# hdreader.net
KiCad netlist of a schematic drawn in EAGLE
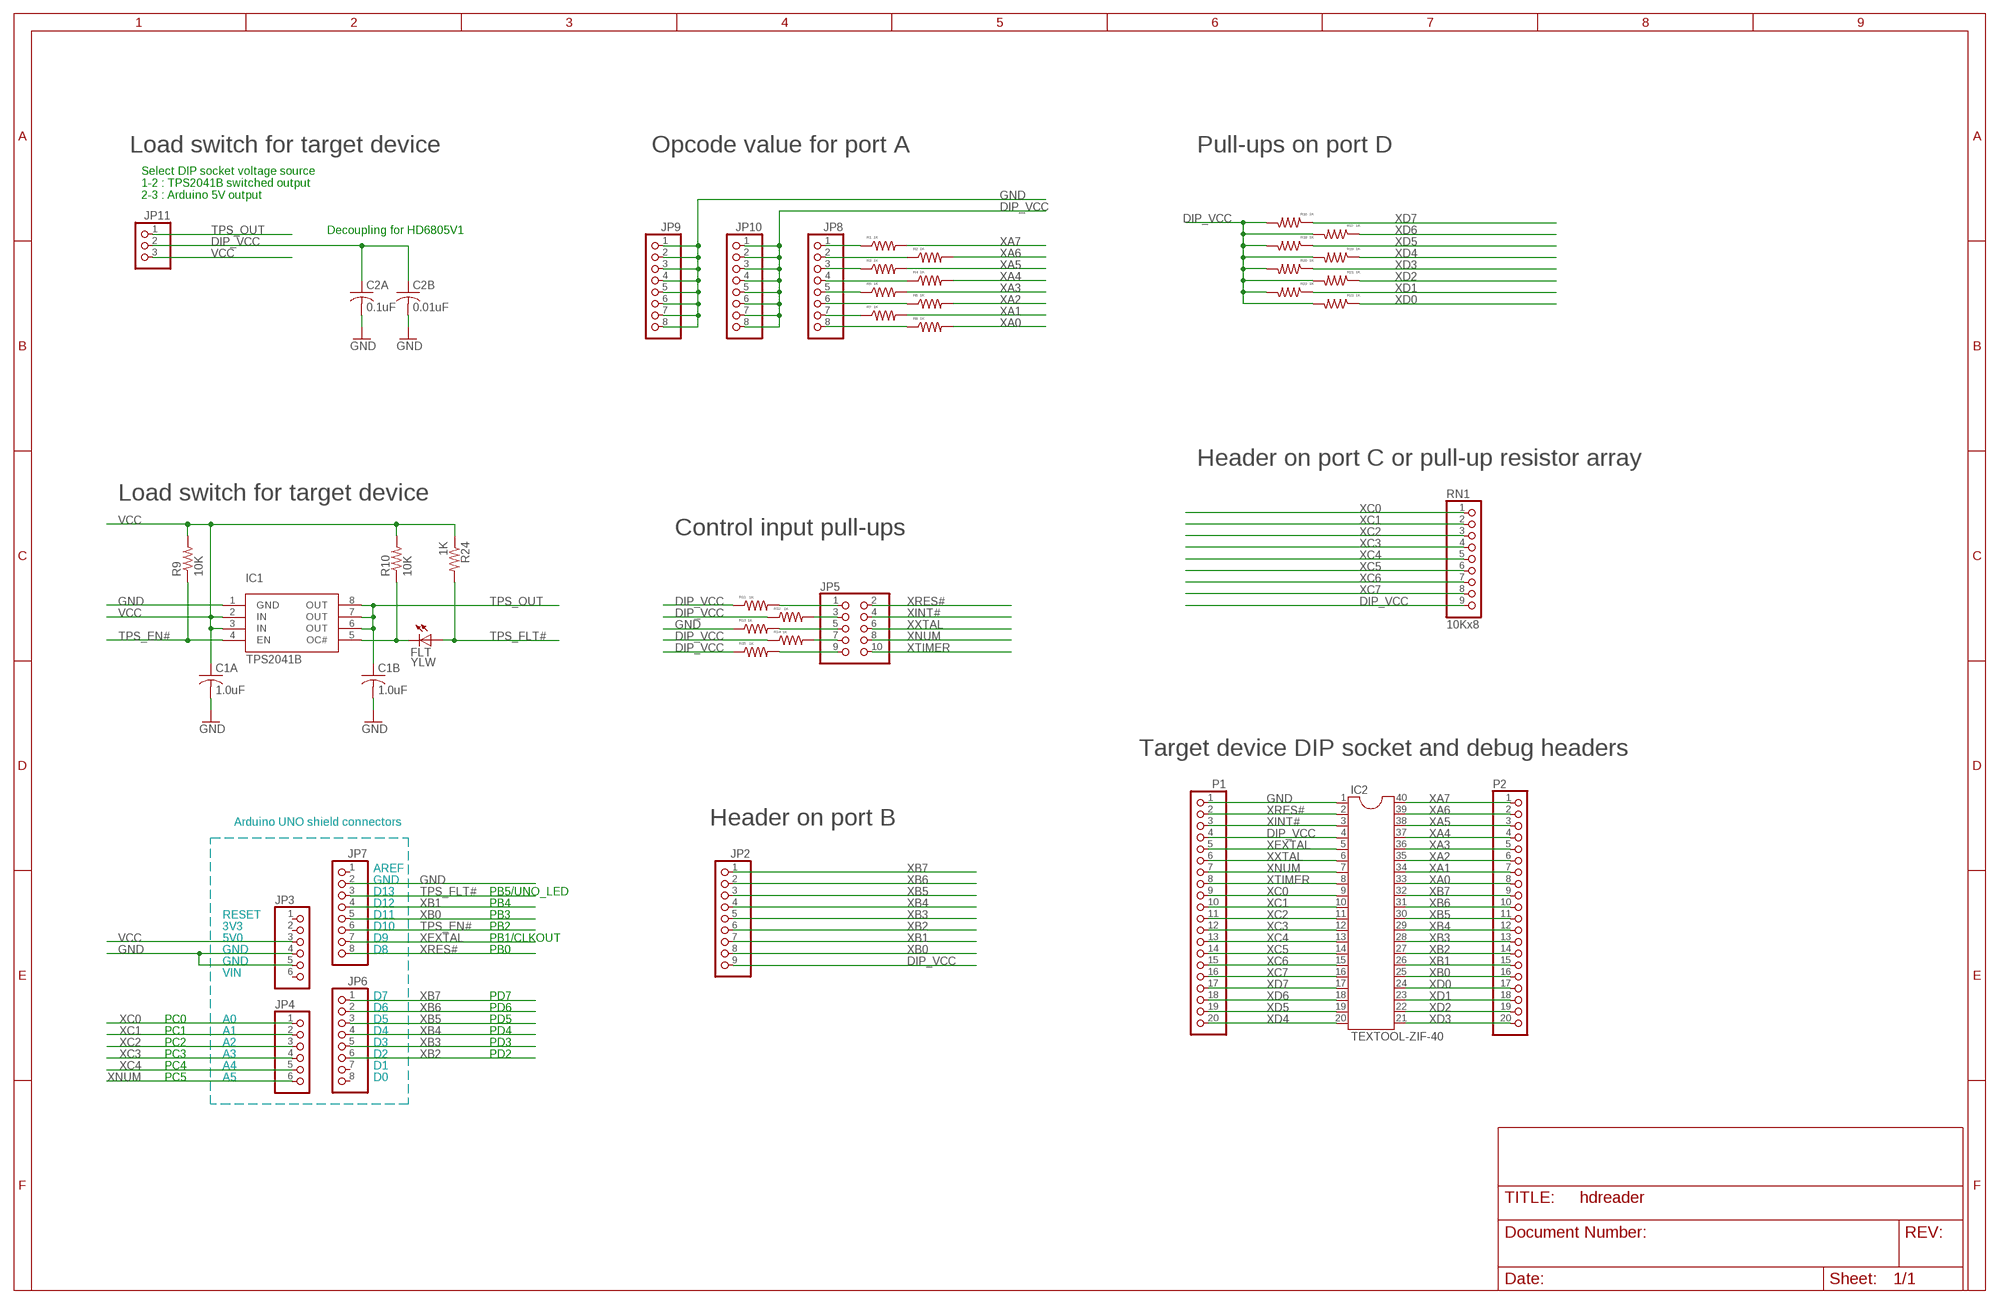
[diagram p0: schematic, sheet 1]

(export (version "E")
  (design (tool "Eeschema 10.0.6"))
  (components
    (comp (ref "C1A")
      (value "1.0uF")
      (footprint "eagle-import:C0603")
      (libsource (lib "eagle-import") (part "C-USC0603"))
    )
    (comp (ref "C1B")
      (value "1.0uF")
      (footprint "eagle-import:C0603")
      (libsource (lib "eagle-import") (part "C-USC0603"))
    )
    (comp (ref "C2A")
      (value "0.1uF")
      (footprint "eagle-import:C0603")
      (libsource (lib "eagle-import") (part "C-USC0603"))
    )
    (comp (ref "C2B")
      (value "0.01uF")
      (footprint "eagle-import:C0603")
      (libsource (lib "eagle-import") (part "C-USC0603"))
    )
    (comp (ref "FLT")
      (value "YLW")
      (footprint "eagle-import:LED5MM")
      (libsource (lib "eagle-import") (part "LED5MM"))
    )
    (comp (ref "IC1")
      (value "TPS2041B")
      (footprint "eagle-import:SOIC8")
      (libsource (lib "eagle-import") (part "TPS2051D"))
    )
    (comp (ref "IC2")
      (value "TEXTOOL-ZIF-40")
      (footprint "eagle-import:TEXTOOL-DIP-40")
      (libsource (lib "eagle-import") (part "TEXTOOL-ZIF-40"))
    )
    (comp (ref "JP2")
      (value "PINHD-1X9")
      (footprint "eagle-import:1X09")
      (libsource (lib "eagle-import") (part "PINHD-1X9"))
    )
    (comp (ref "JP3")
      (value "PINHD-1X6")
      (footprint "eagle-import:1X06")
      (libsource (lib "eagle-import") (part "PINHD-1X6"))
    )
    (comp (ref "JP4")
      (value "PINHD-1X6")
      (footprint "eagle-import:1X06")
      (libsource (lib "eagle-import") (part "PINHD-1X6"))
    )
    (comp (ref "JP5")
      (value "PINHD-2X5")
      (footprint "eagle-import:2X05")
      (libsource (lib "eagle-import") (part "PINHD-2X5"))
    )
    (comp (ref "JP6")
      (value "PINHD-1X8")
      (footprint "eagle-import:1X08")
      (libsource (lib "eagle-import") (part "PINHD-1X8"))
    )
    (comp (ref "JP7")
      (value "PINHD-1X8")
      (footprint "eagle-import:1X08")
      (libsource (lib "eagle-import") (part "PINHD-1X8"))
    )
    (comp (ref "JP8")
      (value "PINHD-1X8")
      (footprint "eagle-import:1X08")
      (libsource (lib "eagle-import") (part "PINHD-1X8"))
    )
    (comp (ref "JP9")
      (value "PINHD-1X8")
      (footprint "eagle-import:1X08")
      (libsource (lib "eagle-import") (part "PINHD-1X8"))
    )
    (comp (ref "JP10")
      (value "PINHD-1X8")
      (footprint "eagle-import:1X08")
      (libsource (lib "eagle-import") (part "PINHD-1X8"))
    )
    (comp (ref "JP11")
      (value "PINHD-1X3")
      (footprint "eagle-import:1X03")
      (libsource (lib "eagle-import") (part "PINHD-1X3"))
    )
    (comp (ref "P1")
      (value "PINHD-1X20")
      (footprint "eagle-import:1X20")
      (libsource (lib "eagle-import") (part "PINHD-1X20"))
    )
    (comp (ref "P2")
      (value "PINHD-1X20")
      (footprint "eagle-import:1X20")
      (libsource (lib "eagle-import") (part "PINHD-1X20"))
    )
    (comp (ref "R1")
      (value "1K")
      (footprint "eagle-import:R0603")
      (libsource (lib "eagle-import") (part "R-US_R0603"))
    )
    (comp (ref "R2")
      (value "1K")
      (footprint "eagle-import:R0603")
      (libsource (lib "eagle-import") (part "R-US_R0603"))
    )
    (comp (ref "R3")
      (value "1K")
      (footprint "eagle-import:R0603")
      (libsource (lib "eagle-import") (part "R-US_R0603"))
    )
    (comp (ref "R4")
      (value "1K")
      (footprint "eagle-import:R0603")
      (libsource (lib "eagle-import") (part "R-US_R0603"))
    )
    (comp (ref "R5")
      (value "1K")
      (footprint "eagle-import:R0603")
      (libsource (lib "eagle-import") (part "R-US_R0603"))
    )
    (comp (ref "R6")
      (value "1K")
      (footprint "eagle-import:R0603")
      (libsource (lib "eagle-import") (part "R-US_R0603"))
    )
    (comp (ref "R7")
      (value "1K")
      (footprint "eagle-import:R0603")
      (libsource (lib "eagle-import") (part "R-US_R0603"))
    )
    (comp (ref "R8")
      (value "1K")
      (footprint "eagle-import:R0603")
      (libsource (lib "eagle-import") (part "R-US_R0603"))
    )
    (comp (ref "R9")
      (value "10K")
      (footprint "eagle-import:R0603")
      (libsource (lib "eagle-import") (part "R-US_R0603"))
    )
    (comp (ref "R10")
      (value "10K")
      (footprint "eagle-import:R0603")
      (libsource (lib "eagle-import") (part "R-US_R0603"))
    )
    (comp (ref "R11")
      (value "1K")
      (footprint "eagle-import:R0603")
      (libsource (lib "eagle-import") (part "R-US_R0603"))
    )
    (comp (ref "R12")
      (value "1K")
      (footprint "eagle-import:R0603")
      (libsource (lib "eagle-import") (part "R-US_R0603"))
    )
    (comp (ref "R13")
      (value "1K")
      (footprint "eagle-import:R0603")
      (libsource (lib "eagle-import") (part "R-US_R0603"))
    )
    (comp (ref "R14")
      (value "1K")
      (footprint "eagle-import:R0603")
      (libsource (lib "eagle-import") (part "R-US_R0603"))
    )
    (comp (ref "R15")
      (value "1K")
      (footprint "eagle-import:R0603")
      (libsource (lib "eagle-import") (part "R-US_R0603"))
    )
    (comp (ref "R16")
      (value "1K")
      (footprint "eagle-import:R0603")
      (libsource (lib "eagle-import") (part "R-US_R0603"))
    )
    (comp (ref "R17")
      (value "1K")
      (footprint "eagle-import:R0603")
      (libsource (lib "eagle-import") (part "R-US_R0603"))
    )
    (comp (ref "R18")
      (value "1K")
      (footprint "eagle-import:R0603")
      (libsource (lib "eagle-import") (part "R-US_R0603"))
    )
    (comp (ref "R19")
      (value "1K")
      (footprint "eagle-import:R0603")
      (libsource (lib "eagle-import") (part "R-US_R0603"))
    )
    (comp (ref "R20")
      (value "1K")
      (footprint "eagle-import:R0603")
      (libsource (lib "eagle-import") (part "R-US_R0603"))
    )
    (comp (ref "R21")
      (value "1K")
      (footprint "eagle-import:R0603")
      (libsource (lib "eagle-import") (part "R-US_R0603"))
    )
    (comp (ref "R22")
      (value "1K")
      (footprint "eagle-import:R0603")
      (libsource (lib "eagle-import") (part "R-US_R0603"))
    )
    (comp (ref "R23")
      (value "1K")
      (footprint "eagle-import:R0603")
      (libsource (lib "eagle-import") (part "R-US_R0603"))
    )
    (comp (ref "R24")
      (value "1K")
      (footprint "eagle-import:R0603")
      (libsource (lib "eagle-import") (part "R-US_R0603"))
    )
    (comp (ref "RN1")
      (value "10Kx8")
      (footprint "eagle-import:1X09")
      (libsource (lib "eagle-import") (part "PINHD-1X9"))
    )
  )
  (nets
    (net (code "1") (name "/DIP_VCC") (class "Default")
      (node (ref "C2A") (pin "1") (pinfunction "1_1") (pintype "passive"))
      (node (ref "C2B") (pin "1") (pinfunction "1_1") (pintype "passive"))
      (node (ref "IC2") (pin "4") (pinfunction "4_4") (pintype "passive"))
      (node (ref "JP10") (pin "1") (pinfunction "1_1") (pintype "passive"))
      (node (ref "JP10") (pin "2") (pinfunction "2_2") (pintype "passive"))
      (node (ref "JP10") (pin "3") (pinfunction "3_3") (pintype "passive"))
      (node (ref "JP10") (pin "4") (pinfunction "4_4") (pintype "passive"))
      (node (ref "JP10") (pin "5") (pinfunction "5_5") (pintype "passive"))
      (node (ref "JP10") (pin "6") (pinfunction "6_6") (pintype "passive"))
      (node (ref "JP10") (pin "7") (pinfunction "7_7") (pintype "passive"))
      (node (ref "JP10") (pin "8") (pinfunction "8_8") (pintype "passive"))
      (node (ref "JP11") (pin "2") (pinfunction "2_2") (pintype "passive"))
      (node (ref "JP2") (pin "9") (pinfunction "9_9") (pintype "passive"))
      (node (ref "P1") (pin "4") (pinfunction "4_4") (pintype "passive"))
      (node (ref "R11") (pin "1") (pinfunction "1_1") (pintype "passive"))
      (node (ref "R12") (pin "1") (pinfunction "1_1") (pintype "passive"))
      (node (ref "R14") (pin "1") (pinfunction "1_1") (pintype "passive"))
      (node (ref "R15") (pin "1") (pinfunction "1_1") (pintype "passive"))
      (node (ref "R16") (pin "2") (pinfunction "2_2") (pintype "passive"))
      (node (ref "R17") (pin "2") (pinfunction "2_2") (pintype "passive"))
      (node (ref "R18") (pin "2") (pinfunction "2_2") (pintype "passive"))
      (node (ref "R19") (pin "2") (pinfunction "2_2") (pintype "passive"))
      (node (ref "R20") (pin "2") (pinfunction "2_2") (pintype "passive"))
      (node (ref "R21") (pin "2") (pinfunction "2_2") (pintype "passive"))
      (node (ref "R22") (pin "2") (pinfunction "2_2") (pintype "passive"))
      (node (ref "R23") (pin "2") (pinfunction "2_2") (pintype "passive"))
      (node (ref "RN1") (pin "9") (pinfunction "9_9") (pintype "passive"))
    )
    (net (code "2") (name "/TPS_EN#") (class "Default")
      (node (ref "IC1") (pin "4") (pinfunction "EN_4") (pintype "input"))
      (node (ref "JP7") (pin "6") (pinfunction "6_6") (pintype "passive"))
      (node (ref "R9") (pin "1") (pinfunction "1_1") (pintype "passive"))
    )
    (net (code "3") (name "/TPS_FLT#") (class "Default")
      (node (ref "FLT") (pin "K") (pinfunction "C_K") (pintype "passive"))
      (node (ref "IC1") (pin "5") (pinfunction "OC#_5") (pintype "open_collector"))
      (node (ref "JP7") (pin "3") (pinfunction "3_3") (pintype "passive"))
      (node (ref "R10") (pin "1") (pinfunction "1_1") (pintype "passive"))
    )
    (net (code "4") (name "/TPS_OUT") (class "Default")
      (node (ref "C1B") (pin "1") (pinfunction "1_1") (pintype "passive"))
      (node (ref "IC1") (pin "6") (pinfunction "OUT_6") (pintype "power_in"))
      (node (ref "IC1") (pin "7") (pinfunction "OUT_7") (pintype "power_in"))
      (node (ref "IC1") (pin "8") (pinfunction "OUT_8") (pintype "power_in"))
      (node (ref "JP11") (pin "1") (pinfunction "1_1") (pintype "passive"))
    )
    (net (code "5") (name "/VCC") (class "Default")
      (node (ref "C1A") (pin "1") (pinfunction "1_1") (pintype "passive"))
      (node (ref "IC1") (pin "2") (pinfunction "IN_2") (pintype "power_in"))
      (node (ref "IC1") (pin "3") (pinfunction "IN_3") (pintype "power_in"))
      (node (ref "JP11") (pin "3") (pinfunction "3_3") (pintype "passive"))
      (node (ref "JP3") (pin "3") (pinfunction "3_3") (pintype "passive"))
      (node (ref "R10") (pin "2") (pinfunction "2_2") (pintype "passive"))
      (node (ref "R24") (pin "1") (pinfunction "1_1") (pintype "passive"))
      (node (ref "R9") (pin "2") (pinfunction "2_2") (pintype "passive"))
    )
    (net (code "6") (name "/XA0") (class "Default")
      (node (ref "IC2") (pin "33") (pinfunction "33_33") (pintype "passive"))
      (node (ref "P2") (pin "8") (pinfunction "8_8") (pintype "passive"))
      (node (ref "R8") (pin "2") (pinfunction "2_2") (pintype "passive"))
    )
    (net (code "7") (name "/XA1") (class "Default")
      (node (ref "IC2") (pin "34") (pinfunction "34_34") (pintype "passive"))
      (node (ref "P2") (pin "7") (pinfunction "7_7") (pintype "passive"))
      (node (ref "R7") (pin "2") (pinfunction "2_2") (pintype "passive"))
    )
    (net (code "8") (name "/XA2") (class "Default")
      (node (ref "IC2") (pin "35") (pinfunction "35_35") (pintype "passive"))
      (node (ref "P2") (pin "6") (pinfunction "6_6") (pintype "passive"))
      (node (ref "R6") (pin "2") (pinfunction "2_2") (pintype "passive"))
    )
    (net (code "9") (name "/XA3") (class "Default")
      (node (ref "IC2") (pin "36") (pinfunction "36_36") (pintype "passive"))
      (node (ref "P2") (pin "5") (pinfunction "5_5") (pintype "passive"))
      (node (ref "R5") (pin "2") (pinfunction "2_2") (pintype "passive"))
    )
    (net (code "10") (name "/XA4") (class "Default")
      (node (ref "IC2") (pin "37") (pinfunction "37_37") (pintype "passive"))
      (node (ref "P2") (pin "4") (pinfunction "4_4") (pintype "passive"))
      (node (ref "R4") (pin "2") (pinfunction "2_2") (pintype "passive"))
    )
    (net (code "11") (name "/XA5") (class "Default")
      (node (ref "IC2") (pin "38") (pinfunction "38_38") (pintype "passive"))
      (node (ref "P2") (pin "3") (pinfunction "3_3") (pintype "passive"))
      (node (ref "R3") (pin "2") (pinfunction "2_2") (pintype "passive"))
    )
    (net (code "12") (name "/XA6") (class "Default")
      (node (ref "IC2") (pin "39") (pinfunction "39_39") (pintype "passive"))
      (node (ref "P2") (pin "2") (pinfunction "2_2") (pintype "passive"))
      (node (ref "R2") (pin "2") (pinfunction "2_2") (pintype "passive"))
    )
    (net (code "13") (name "/XA7") (class "Default")
      (node (ref "IC2") (pin "40") (pinfunction "40_40") (pintype "passive"))
      (node (ref "P2") (pin "1") (pinfunction "1_1") (pintype "passive"))
      (node (ref "R1") (pin "2") (pinfunction "2_2") (pintype "passive"))
    )
    (net (code "14") (name "/XB0") (class "Default")
      (node (ref "IC2") (pin "25") (pinfunction "25_25") (pintype "passive"))
      (node (ref "JP2") (pin "8") (pinfunction "8_8") (pintype "passive"))
      (node (ref "JP7") (pin "5") (pinfunction "5_5") (pintype "passive"))
      (node (ref "P2") (pin "16") (pinfunction "16_16") (pintype "passive"))
    )
    (net (code "15") (name "/XB1") (class "Default")
      (node (ref "IC2") (pin "26") (pinfunction "26_26") (pintype "passive"))
      (node (ref "JP2") (pin "7") (pinfunction "7_7") (pintype "passive"))
      (node (ref "JP7") (pin "4") (pinfunction "4_4") (pintype "passive"))
      (node (ref "P2") (pin "15") (pinfunction "15_15") (pintype "passive"))
    )
    (net (code "16") (name "/XB2") (class "Default")
      (node (ref "IC2") (pin "27") (pinfunction "27_27") (pintype "passive"))
      (node (ref "JP2") (pin "6") (pinfunction "6_6") (pintype "passive"))
      (node (ref "JP6") (pin "6") (pinfunction "6_6") (pintype "passive"))
      (node (ref "P2") (pin "14") (pinfunction "14_14") (pintype "passive"))
    )
    (net (code "17") (name "/XB3") (class "Default")
      (node (ref "IC2") (pin "28") (pinfunction "28_28") (pintype "passive"))
      (node (ref "JP2") (pin "5") (pinfunction "5_5") (pintype "passive"))
      (node (ref "JP6") (pin "5") (pinfunction "5_5") (pintype "passive"))
      (node (ref "P2") (pin "13") (pinfunction "13_13") (pintype "passive"))
    )
    (net (code "18") (name "/XB4") (class "Default")
      (node (ref "IC2") (pin "29") (pinfunction "29_29") (pintype "passive"))
      (node (ref "JP2") (pin "4") (pinfunction "4_4") (pintype "passive"))
      (node (ref "JP6") (pin "4") (pinfunction "4_4") (pintype "passive"))
      (node (ref "P2") (pin "12") (pinfunction "12_12") (pintype "passive"))
    )
    (net (code "19") (name "/XB5") (class "Default")
      (node (ref "IC2") (pin "30") (pinfunction "30_30") (pintype "passive"))
      (node (ref "JP2") (pin "3") (pinfunction "3_3") (pintype "passive"))
      (node (ref "JP6") (pin "3") (pinfunction "3_3") (pintype "passive"))
      (node (ref "P2") (pin "11") (pinfunction "11_11") (pintype "passive"))
    )
    (net (code "20") (name "/XB6") (class "Default")
      (node (ref "IC2") (pin "31") (pinfunction "31_31") (pintype "passive"))
      (node (ref "JP2") (pin "2") (pinfunction "2_2") (pintype "passive"))
      (node (ref "JP6") (pin "2") (pinfunction "2_2") (pintype "passive"))
      (node (ref "P2") (pin "10") (pinfunction "10_10") (pintype "passive"))
    )
    (net (code "21") (name "/XB7") (class "Default")
      (node (ref "IC2") (pin "32") (pinfunction "32_32") (pintype "passive"))
      (node (ref "JP2") (pin "1") (pinfunction "1_1") (pintype "passive"))
      (node (ref "JP6") (pin "1") (pinfunction "1_1") (pintype "passive"))
      (node (ref "P2") (pin "9") (pinfunction "9_9") (pintype "passive"))
    )
    (net (code "22") (name "/XC0") (class "Default")
      (node (ref "IC2") (pin "9") (pinfunction "9_9") (pintype "passive"))
      (node (ref "JP4") (pin "1") (pinfunction "1_1") (pintype "passive"))
      (node (ref "P1") (pin "9") (pinfunction "9_9") (pintype "passive"))
      (node (ref "RN1") (pin "1") (pinfunction "1_1") (pintype "passive"))
    )
    (net (code "23") (name "/XC1") (class "Default")
      (node (ref "IC2") (pin "10") (pinfunction "10_10") (pintype "passive"))
      (node (ref "JP4") (pin "2") (pinfunction "2_2") (pintype "passive"))
      (node (ref "P1") (pin "10") (pinfunction "10_10") (pintype "passive"))
      (node (ref "RN1") (pin "2") (pinfunction "2_2") (pintype "passive"))
    )
    (net (code "24") (name "/XC2") (class "Default")
      (node (ref "IC2") (pin "11") (pinfunction "11_11") (pintype "passive"))
      (node (ref "JP4") (pin "3") (pinfunction "3_3") (pintype "passive"))
      (node (ref "P1") (pin "11") (pinfunction "11_11") (pintype "passive"))
      (node (ref "RN1") (pin "3") (pinfunction "3_3") (pintype "passive"))
    )
    (net (code "25") (name "/XC3") (class "Default")
      (node (ref "IC2") (pin "12") (pinfunction "12_12") (pintype "passive"))
      (node (ref "JP4") (pin "4") (pinfunction "4_4") (pintype "passive"))
      (node (ref "P1") (pin "12") (pinfunction "12_12") (pintype "passive"))
      (node (ref "RN1") (pin "4") (pinfunction "4_4") (pintype "passive"))
    )
    (net (code "26") (name "/XC4") (class "Default")
      (node (ref "IC2") (pin "13") (pinfunction "13_13") (pintype "passive"))
      (node (ref "JP4") (pin "5") (pinfunction "5_5") (pintype "passive"))
      (node (ref "P1") (pin "13") (pinfunction "13_13") (pintype "passive"))
      (node (ref "RN1") (pin "5") (pinfunction "5_5") (pintype "passive"))
    )
    (net (code "27") (name "/XC5") (class "Default")
      (node (ref "IC2") (pin "14") (pinfunction "14_14") (pintype "passive"))
      (node (ref "P1") (pin "14") (pinfunction "14_14") (pintype "passive"))
      (node (ref "RN1") (pin "6") (pinfunction "6_6") (pintype "passive"))
    )
    (net (code "28") (name "/XC6") (class "Default")
      (node (ref "IC2") (pin "15") (pinfunction "15_15") (pintype "passive"))
      (node (ref "P1") (pin "15") (pinfunction "15_15") (pintype "passive"))
      (node (ref "RN1") (pin "7") (pinfunction "7_7") (pintype "passive"))
    )
    (net (code "29") (name "/XC7") (class "Default")
      (node (ref "IC2") (pin "16") (pinfunction "16_16") (pintype "passive"))
      (node (ref "P1") (pin "16") (pinfunction "16_16") (pintype "passive"))
      (node (ref "RN1") (pin "8") (pinfunction "8_8") (pintype "passive"))
    )
    (net (code "30") (name "/XD0") (class "Default")
      (node (ref "IC2") (pin "24") (pinfunction "24_24") (pintype "passive"))
      (node (ref "P2") (pin "17") (pinfunction "17_17") (pintype "passive"))
      (node (ref "R23") (pin "1") (pinfunction "1_1") (pintype "passive"))
    )
    (net (code "31") (name "/XD1") (class "Default")
      (node (ref "IC2") (pin "23") (pinfunction "23_23") (pintype "passive"))
      (node (ref "P2") (pin "18") (pinfunction "18_18") (pintype "passive"))
      (node (ref "R22") (pin "1") (pinfunction "1_1") (pintype "passive"))
    )
    (net (code "32") (name "/XD2") (class "Default")
      (node (ref "IC2") (pin "22") (pinfunction "22_22") (pintype "passive"))
      (node (ref "P2") (pin "19") (pinfunction "19_19") (pintype "passive"))
      (node (ref "R21") (pin "1") (pinfunction "1_1") (pintype "passive"))
    )
    (net (code "33") (name "/XD3") (class "Default")
      (node (ref "IC2") (pin "21") (pinfunction "21_21") (pintype "passive"))
      (node (ref "P2") (pin "20") (pinfunction "20_20") (pintype "passive"))
      (node (ref "R20") (pin "1") (pinfunction "1_1") (pintype "passive"))
    )
    (net (code "34") (name "/XD4") (class "Default")
      (node (ref "IC2") (pin "20") (pinfunction "20_20") (pintype "passive"))
      (node (ref "P1") (pin "20") (pinfunction "20_20") (pintype "passive"))
      (node (ref "R19") (pin "1") (pinfunction "1_1") (pintype "passive"))
    )
    (net (code "35") (name "/XD5") (class "Default")
      (node (ref "IC2") (pin "19") (pinfunction "19_19") (pintype "passive"))
      (node (ref "P1") (pin "19") (pinfunction "19_19") (pintype "passive"))
      (node (ref "R18") (pin "1") (pinfunction "1_1") (pintype "passive"))
    )
    (net (code "36") (name "/XD6") (class "Default")
      (node (ref "IC2") (pin "18") (pinfunction "18_18") (pintype "passive"))
      (node (ref "P1") (pin "18") (pinfunction "18_18") (pintype "passive"))
      (node (ref "R17") (pin "1") (pinfunction "1_1") (pintype "passive"))
    )
    (net (code "37") (name "/XD7") (class "Default")
      (node (ref "IC2") (pin "17") (pinfunction "17_17") (pintype "passive"))
      (node (ref "P1") (pin "17") (pinfunction "17_17") (pintype "passive"))
      (node (ref "R16") (pin "1") (pinfunction "1_1") (pintype "passive"))
    )
    (net (code "38") (name "/XEXTAL") (class "Default")
      (node (ref "IC2") (pin "5") (pinfunction "5_5") (pintype "passive"))
      (node (ref "JP7") (pin "7") (pinfunction "7_7") (pintype "passive"))
      (node (ref "P1") (pin "5") (pinfunction "5_5") (pintype "passive"))
    )
    (net (code "39") (name "/XINT#") (class "Default")
      (node (ref "IC2") (pin "3") (pinfunction "3_3") (pintype "passive"))
      (node (ref "JP5") (pin "4") (pinfunction "4_4") (pintype "passive"))
      (node (ref "P1") (pin "3") (pinfunction "3_3") (pintype "passive"))
    )
    (net (code "40") (name "/XNUM") (class "Default")
      (node (ref "IC2") (pin "7") (pinfunction "7_7") (pintype "passive"))
      (node (ref "JP4") (pin "6") (pinfunction "6_6") (pintype "passive"))
      (node (ref "JP5") (pin "8") (pinfunction "8_8") (pintype "passive"))
      (node (ref "P1") (pin "7") (pinfunction "7_7") (pintype "passive"))
    )
    (net (code "41") (name "/XRES#") (class "Default")
      (node (ref "IC2") (pin "2") (pinfunction "2_2") (pintype "passive"))
      (node (ref "JP5") (pin "2") (pinfunction "2_2") (pintype "passive"))
      (node (ref "JP7") (pin "8") (pinfunction "8_8") (pintype "passive"))
      (node (ref "P1") (pin "2") (pinfunction "2_2") (pintype "passive"))
    )
    (net (code "42") (name "/XTIMER") (class "Default")
      (node (ref "IC2") (pin "8") (pinfunction "8_8") (pintype "passive"))
      (node (ref "JP5") (pin "10") (pinfunction "10_10") (pintype "passive"))
      (node (ref "P1") (pin "8") (pinfunction "8_8") (pintype "passive"))
    )
    (net (code "43") (name "/XXTAL") (class "Default")
      (node (ref "IC2") (pin "6") (pinfunction "6_6") (pintype "passive"))
      (node (ref "JP5") (pin "6") (pinfunction "6_6") (pintype "passive"))
      (node (ref "P1") (pin "6") (pinfunction "6_6") (pintype "passive"))
    )
    (net (code "44") (name "GND") (class "Default")
      (node (ref "C1A") (pin "2") (pinfunction "2_2") (pintype "passive"))
      (node (ref "C1B") (pin "2") (pinfunction "2_2") (pintype "passive"))
      (node (ref "C2A") (pin "2") (pinfunction "2_2") (pintype "passive"))
      (node (ref "C2B") (pin "2") (pinfunction "2_2") (pintype "passive"))
      (node (ref "IC1") (pin "1") (pinfunction "GND_1") (pintype "power_in"))
      (node (ref "IC2") (pin "1") (pinfunction "1_1") (pintype "passive"))
      (node (ref "JP3") (pin "4") (pinfunction "4_4") (pintype "passive"))
      (node (ref "JP3") (pin "5") (pinfunction "5_5") (pintype "passive"))
      (node (ref "JP7") (pin "2") (pinfunction "2_2") (pintype "passive"))
      (node (ref "JP9") (pin "1") (pinfunction "1_1") (pintype "passive"))
      (node (ref "JP9") (pin "2") (pinfunction "2_2") (pintype "passive"))
      (node (ref "JP9") (pin "3") (pinfunction "3_3") (pintype "passive"))
      (node (ref "JP9") (pin "4") (pinfunction "4_4") (pintype "passive"))
      (node (ref "JP9") (pin "5") (pinfunction "5_5") (pintype "passive"))
      (node (ref "JP9") (pin "6") (pinfunction "6_6") (pintype "passive"))
      (node (ref "JP9") (pin "7") (pinfunction "7_7") (pintype "passive"))
      (node (ref "JP9") (pin "8") (pinfunction "8_8") (pintype "passive"))
      (node (ref "P1") (pin "1") (pinfunction "1_1") (pintype "passive"))
      (node (ref "R13") (pin "1") (pinfunction "1_1") (pintype "passive"))
    )
    (net (code "45") (name "Net-(FLT-PadA)") (class "Default")
      (node (ref "FLT") (pin "A") (pinfunction "A_A") (pintype "passive"))
      (node (ref "R24") (pin "2") (pinfunction "2_2") (pintype "passive"))
    )
    (net (code "46") (name "Net-(JP5-Pad1)") (class "Default")
      (node (ref "JP5") (pin "1") (pinfunction "1_1") (pintype "passive"))
      (node (ref "R11") (pin "2") (pinfunction "2_2") (pintype "passive"))
    )
    (net (code "47") (name "Net-(JP5-Pad3)") (class "Default")
      (node (ref "JP5") (pin "3") (pinfunction "3_3") (pintype "passive"))
      (node (ref "R12") (pin "2") (pinfunction "2_2") (pintype "passive"))
    )
    (net (code "48") (name "Net-(JP5-Pad5)") (class "Default")
      (node (ref "JP5") (pin "5") (pinfunction "5_5") (pintype "passive"))
      (node (ref "R13") (pin "2") (pinfunction "2_2") (pintype "passive"))
    )
    (net (code "49") (name "Net-(JP5-Pad7)") (class "Default")
      (node (ref "JP5") (pin "7") (pinfunction "7_7") (pintype "passive"))
      (node (ref "R14") (pin "2") (pinfunction "2_2") (pintype "passive"))
    )
    (net (code "50") (name "Net-(JP5-Pad9)") (class "Default")
      (node (ref "JP5") (pin "9") (pinfunction "9_9") (pintype "passive"))
      (node (ref "R15") (pin "2") (pinfunction "2_2") (pintype "passive"))
    )
    (net (code "51") (name "Net-(JP8-Pad1)") (class "Default")
      (node (ref "JP8") (pin "1") (pinfunction "1_1") (pintype "passive"))
      (node (ref "R1") (pin "1") (pinfunction "1_1") (pintype "passive"))
    )
    (net (code "52") (name "Net-(JP8-Pad2)") (class "Default")
      (node (ref "JP8") (pin "2") (pinfunction "2_2") (pintype "passive"))
      (node (ref "R2") (pin "1") (pinfunction "1_1") (pintype "passive"))
    )
    (net (code "53") (name "Net-(JP8-Pad3)") (class "Default")
      (node (ref "JP8") (pin "3") (pinfunction "3_3") (pintype "passive"))
      (node (ref "R3") (pin "1") (pinfunction "1_1") (pintype "passive"))
    )
    (net (code "54") (name "Net-(JP8-Pad4)") (class "Default")
      (node (ref "JP8") (pin "4") (pinfunction "4_4") (pintype "passive"))
      (node (ref "R4") (pin "1") (pinfunction "1_1") (pintype "passive"))
    )
    (net (code "55") (name "Net-(JP8-Pad5)") (class "Default")
      (node (ref "JP8") (pin "5") (pinfunction "5_5") (pintype "passive"))
      (node (ref "R5") (pin "1") (pinfunction "1_1") (pintype "passive"))
    )
    (net (code "56") (name "Net-(JP8-Pad6)") (class "Default")
      (node (ref "JP8") (pin "6") (pinfunction "6_6") (pintype "passive"))
      (node (ref "R6") (pin "1") (pinfunction "1_1") (pintype "passive"))
    )
    (net (code "57") (name "Net-(JP8-Pad7)") (class "Default")
      (node (ref "JP8") (pin "7") (pinfunction "7_7") (pintype "passive"))
      (node (ref "R7") (pin "1") (pinfunction "1_1") (pintype "passive"))
    )
    (net (code "58") (name "Net-(JP8-Pad8)") (class "Default")
      (node (ref "JP8") (pin "8") (pinfunction "8_8") (pintype "passive"))
      (node (ref "R8") (pin "1") (pinfunction "1_1") (pintype "passive"))
    )
    (net (code "59") (name "unconnected-(JP3-Pad1)") (class "Default")
      (node (ref "JP3") (pin "1") (pinfunction "1_1") (pintype "passive"))
    )
    (net (code "60") (name "unconnected-(JP3-Pad2)") (class "Default")
      (node (ref "JP3") (pin "2") (pinfunction "2_2") (pintype "passive"))
    )
    (net (code "61") (name "unconnected-(JP3-Pad6)") (class "Default")
      (node (ref "JP3") (pin "6") (pinfunction "6_6") (pintype "passive"))
    )
    (net (code "62") (name "unconnected-(JP6-Pad7)") (class "Default")
      (node (ref "JP6") (pin "7") (pinfunction "7_7") (pintype "passive"))
    )
    (net (code "63") (name "unconnected-(JP6-Pad8)") (class "Default")
      (node (ref "JP6") (pin "8") (pinfunction "8_8") (pintype "passive"))
    )
    (net (code "64") (name "unconnected-(JP7-Pad1)") (class "Default")
      (node (ref "JP7") (pin "1") (pinfunction "1_1") (pintype "passive"))
    )
  )
)
